# schematic.net
KiCad netlist of a schematic drawn in EAGLE
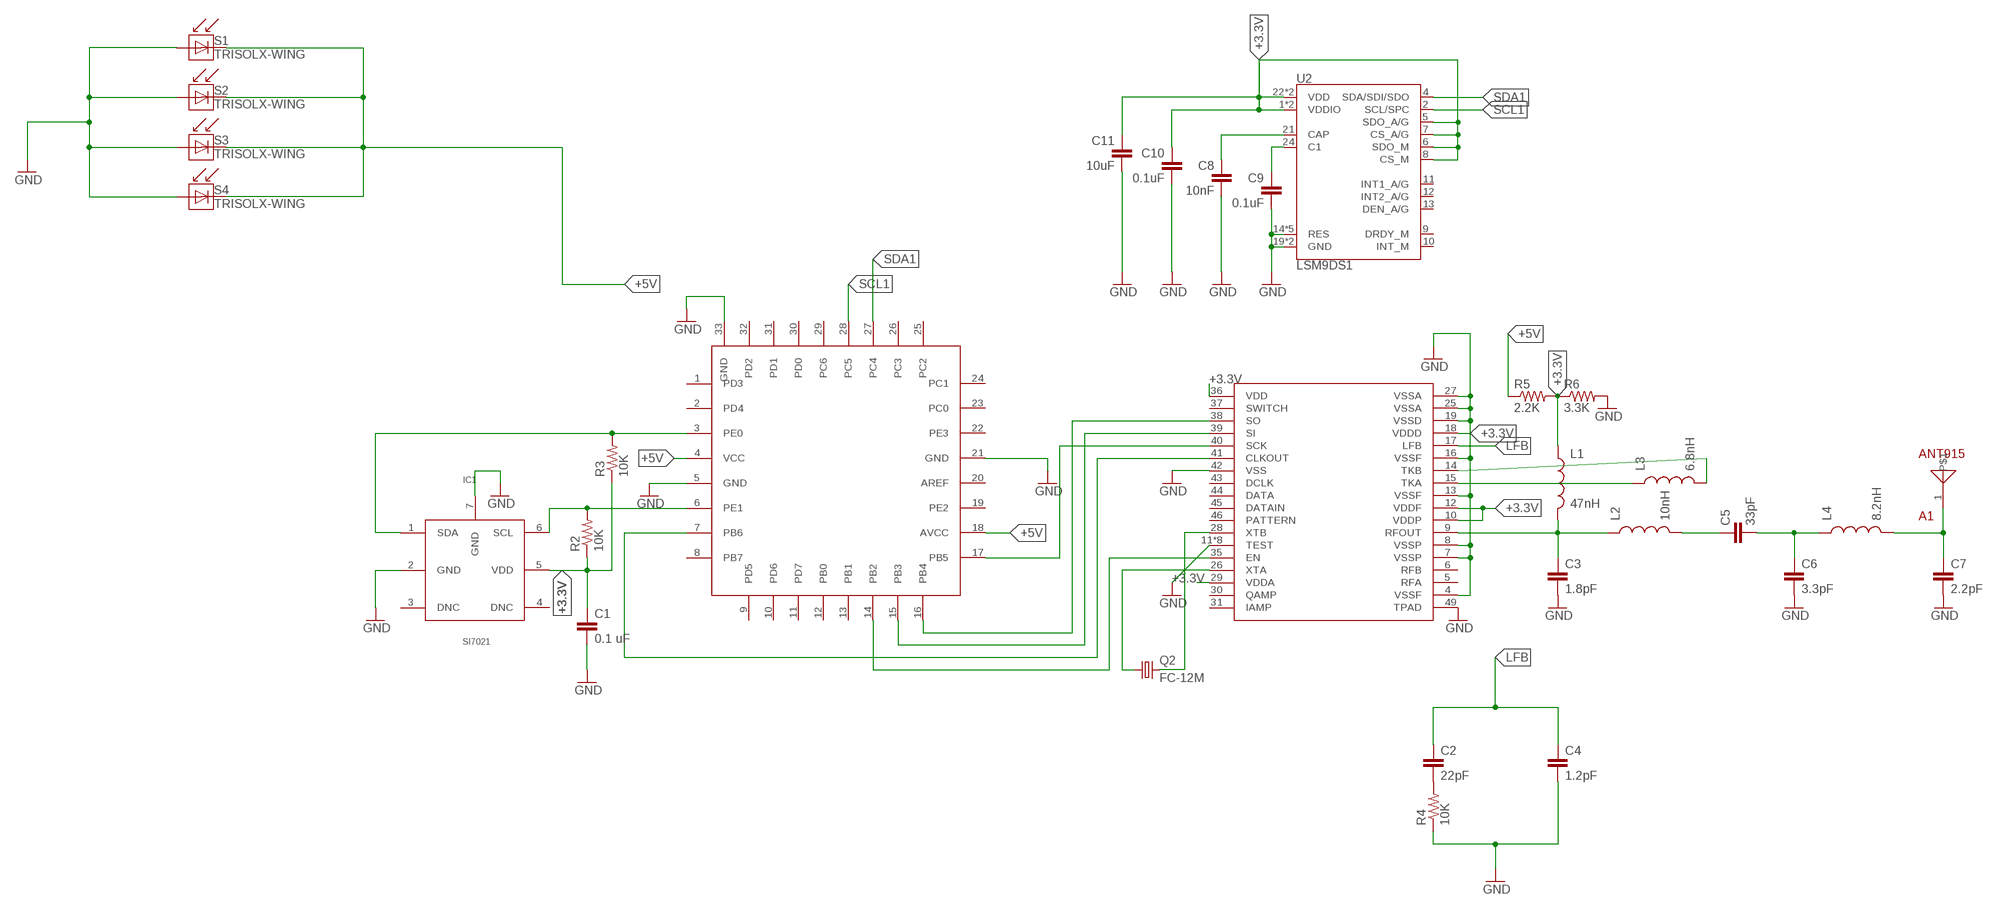
[diagram p0: schematic, sheet 1]

(export (version "E")
  (design (tool "Eeschema 10.0.6"))
  (components
    (comp (ref "A1")
      (value "ANT915")
      (footprint "eagle-import:ANT915")
      (libsource (lib "eagle-import") (part "ANT915"))
    )
    (comp (ref "C1")
      (value "0.1 uF")
      (footprint "eagle-import:0603-CAP")
      (libsource (lib "eagle-import") (part "CAP0603-CAP"))
    )
    (comp (ref "C2")
      (value "22pF")
      (footprint "eagle-import:0603-CAP")
      (libsource (lib "eagle-import") (part "CAP0603-CAP"))
    )
    (comp (ref "C3")
      (value "1.8pF")
      (footprint "eagle-import:0603-CAP")
      (libsource (lib "eagle-import") (part "CAP0603-CAP"))
    )
    (comp (ref "C4")
      (value "1.2pF")
      (footprint "eagle-import:0603-CAP")
      (libsource (lib "eagle-import") (part "CAP0603-CAP"))
    )
    (comp (ref "C5")
      (value "33pF")
      (footprint "eagle-import:0603-CAP")
      (libsource (lib "eagle-import") (part "CAP0603-CAP"))
    )
    (comp (ref "C6")
      (value "3.3pF")
      (footprint "eagle-import:0603-CAP")
      (libsource (lib "eagle-import") (part "CAP0603-CAP"))
    )
    (comp (ref "C7")
      (value "2.2pF")
      (footprint "eagle-import:0603-CAP")
      (libsource (lib "eagle-import") (part "CAP0603-CAP"))
    )
    (comp (ref "C8")
      (value "10nF")
      (footprint "eagle-import:0603-CAP")
      (libsource (lib "eagle-import") (part "CAP0603-CAP"))
    )
    (comp (ref "C9")
      (value "0.1uF")
      (footprint "eagle-import:0603-CAP")
      (libsource (lib "eagle-import") (part "CAP0603-CAP"))
    )
    (comp (ref "C10")
      (value "0.1uF")
      (footprint "eagle-import:0603-CAP")
      (libsource (lib "eagle-import") (part "CAP0603-CAP"))
    )
    (comp (ref "C11")
      (value "10uF")
      (footprint "eagle-import:0603-CAP")
      (libsource (lib "eagle-import") (part "CAP0603-CAP"))
    )
    (comp (ref "IC1")
      (value "SI7021")
      (footprint "eagle-import:SI7021")
      (libsource (lib "eagle-import") (part "SI7021"))
    )
    (comp (ref "IC2")
      (value "ATMEGA328-PB")
      (footprint "eagle-import:ATMEGA328-PB")
      (libsource (lib "eagle-import") (part "ATMEGA328-PB"))
    )
    (comp (ref "IC3")
      (value "XE1203F")
      (footprint "eagle-import:XE1203F")
      (libsource (lib "eagle-import") (part "XE1203F"))
    )
    (comp (ref "L1")
      (value "47nH")
      (footprint "eagle-import:0603")
      (libsource (lib "eagle-import") (part "INDUCTOR0603"))
    )
    (comp (ref "L2")
      (value "10nH")
      (footprint "eagle-import:0603")
      (libsource (lib "eagle-import") (part "INDUCTOR0603"))
    )
    (comp (ref "L3")
      (value "6.8nH")
      (footprint "eagle-import:0603")
      (libsource (lib "eagle-import") (part "INDUCTOR0603"))
    )
    (comp (ref "L4")
      (value "8.2nH")
      (footprint "eagle-import:0603")
      (libsource (lib "eagle-import") (part "INDUCTOR0603"))
    )
    (comp (ref "Q2")
      (value "FC-12M")
      (footprint "eagle-import:FC-12M")
      (libsource (lib "eagle-import") (part "FC-12M"))
    )
    (comp (ref "R2")
      (value "10K")
      (footprint "eagle-import:0603-RES")
      (libsource (lib "eagle-import") (part "RESISTOR0603-RES"))
    )
    (comp (ref "R3")
      (value "10K")
      (footprint "eagle-import:0603-RES")
      (libsource (lib "eagle-import") (part "RESISTOR0603-RES"))
    )
    (comp (ref "R4")
      (value "10K")
      (footprint "eagle-import:0603-RES")
      (libsource (lib "eagle-import") (part "RESISTOR0603-RES"))
    )
    (comp (ref "R5")
      (value "2.2K")
      (footprint "eagle-import:0603-RES")
      (libsource (lib "eagle-import") (part "RESISTOR0603-RES"))
    )
    (comp (ref "R6")
      (value "3.3K")
      (footprint "eagle-import:0603-RES")
      (libsource (lib "eagle-import") (part "RESISTOR0603-RES"))
    )
    (comp (ref "S1")
      (value "TRISOLX-WING")
      (footprint "eagle-import:TRISOLX-T01")
      (libsource (lib "eagle-import") (part "TRISOLX-WING"))
    )
    (comp (ref "S2")
      (value "TRISOLX-WING")
      (footprint "eagle-import:TRISOLX-T01")
      (libsource (lib "eagle-import") (part "TRISOLX-WING"))
    )
    (comp (ref "S3")
      (value "TRISOLX-WING")
      (footprint "eagle-import:TRISOLX-T01")
      (libsource (lib "eagle-import") (part "TRISOLX-WING"))
    )
    (comp (ref "S4")
      (value "TRISOLX-WING")
      (footprint "eagle-import:TRISOLX-T01")
      (libsource (lib "eagle-import") (part "TRISOLX-WING"))
    )
    (comp (ref "U2")
      (value "LSM9DS1")
      (footprint "eagle-import:LGA24-8X4")
      (libsource (lib "eagle-import") (part "LSM9DS1"))
    )
  )
  (nets
    (net (code "1") (name "+3.3V") (class "Default")
      (node (ref "C1") (pin "1") (pinfunction "1_1") (pintype "passive"))
      (node (ref "C10") (pin "1") (pinfunction "1_1") (pintype "passive"))
      (node (ref "C11") (pin "1") (pinfunction "1_1") (pintype "passive"))
      (node (ref "IC1") (pin "5") (pinfunction "VDD_5") (pintype "bidirectional"))
      (node (ref "IC3") (pin "10") (pinfunction "VDDP_10") (pintype "bidirectional"))
      (node (ref "IC3") (pin "12") (pinfunction "VDDF_12") (pintype "bidirectional"))
      (node (ref "IC3") (pin "18") (pinfunction "VDDD_18") (pintype "bidirectional"))
      (node (ref "IC3") (pin "29") (pinfunction "VDDA_29") (pintype "bidirectional"))
      (node (ref "IC3") (pin "36") (pinfunction "VDD_36") (pintype "bidirectional"))
      (node (ref "L1") (pin "1") (pinfunction "1_1") (pintype "passive"))
      (node (ref "R2") (pin "1") (pinfunction "1_1") (pintype "passive"))
      (node (ref "R3") (pin "1") (pinfunction "1_1") (pintype "passive"))
      (node (ref "R5") (pin "2") (pinfunction "2_2") (pintype "passive"))
      (node (ref "R6") (pin "1") (pinfunction "1_1") (pintype "passive"))
      (node (ref "U2") (pin "1") (pinfunction "VDDIO_1") (pintype "bidirectional"))
      (node (ref "U2") (pin "22") (pinfunction "VDD_22") (pintype "bidirectional"))
      (node (ref "U2") (pin "23") (pinfunction "VDD_23") (pintype "bidirectional"))
      (node (ref "U2") (pin "3") (pinfunction "VDDIO_3") (pintype "bidirectional"))
      (node (ref "U2") (pin "5") (pinfunction "SDO_A/G_5") (pintype "bidirectional"))
      (node (ref "U2") (pin "6") (pinfunction "SDO_M_6") (pintype "bidirectional"))
      (node (ref "U2") (pin "7") (pinfunction "CS_A/G_7") (pintype "bidirectional"))
      (node (ref "U2") (pin "8") (pinfunction "CS_M_8") (pintype "bidirectional"))
    )
    (net (code "2") (name "+5V") (class "Default")
      (node (ref "IC2") (pin "18") (pinfunction "AVCC_18") (pintype "bidirectional"))
      (node (ref "IC2") (pin "4") (pinfunction "VCC_4") (pintype "bidirectional"))
      (node (ref "R5") (pin "1") (pinfunction "1_1") (pintype "passive"))
      (node (ref "S1") (pin "P$2") (pinfunction "C_P$2") (pintype "passive"))
      (node (ref "S2") (pin "P$2") (pinfunction "C_P$2") (pintype "passive"))
      (node (ref "S3") (pin "P$2") (pinfunction "C_P$2") (pintype "passive"))
      (node (ref "S4") (pin "P$2") (pinfunction "C_P$2") (pintype "passive"))
    )
    (net (code "3") (name "GND") (class "Default")
      (node (ref "C1") (pin "2") (pinfunction "2_2") (pintype "passive"))
      (node (ref "C10") (pin "2") (pinfunction "2_2") (pintype "passive"))
      (node (ref "C11") (pin "2") (pinfunction "2_2") (pintype "passive"))
      (node (ref "C3") (pin "2") (pinfunction "2_2") (pintype "passive"))
      (node (ref "C4") (pin "2") (pinfunction "2_2") (pintype "passive"))
      (node (ref "C6") (pin "2") (pinfunction "2_2") (pintype "passive"))
      (node (ref "C7") (pin "2") (pinfunction "2_2") (pintype "passive"))
      (node (ref "C8") (pin "2") (pinfunction "2_2") (pintype "passive"))
      (node (ref "C9") (pin "2") (pinfunction "2_2") (pintype "passive"))
      (node (ref "IC1") (pin "2") (pinfunction "GND_2") (pintype "bidirectional"))
      (node (ref "IC1") (pin "7") (pinfunction "GND_7") (pintype "bidirectional"))
      (node (ref "IC2") (pin "21") (pinfunction "GND_21") (pintype "bidirectional"))
      (node (ref "IC2") (pin "33") (pinfunction "GND_33") (pintype "bidirectional"))
      (node (ref "IC2") (pin "5") (pinfunction "GND_5") (pintype "bidirectional"))
      (node (ref "IC3") (pin "11") (pinfunction "TEST_11") (pintype "bidirectional"))
      (node (ref "IC3") (pin "13") (pinfunction "VSSF_13") (pintype "bidirectional"))
      (node (ref "IC3") (pin "16") (pinfunction "VSSF_16") (pintype "bidirectional"))
      (node (ref "IC3") (pin "19") (pinfunction "VSSD_19") (pintype "bidirectional"))
      (node (ref "IC3") (pin "20") (pinfunction "TEST_20") (pintype "bidirectional"))
      (node (ref "IC3") (pin "21") (pinfunction "TEST_21") (pintype "bidirectional"))
      (node (ref "IC3") (pin "23") (pinfunction "TEST_23") (pintype "bidirectional"))
      (node (ref "IC3") (pin "24") (pinfunction "TEST_24") (pintype "bidirectional"))
      (node (ref "IC3") (pin "25") (pinfunction "VSSA_25") (pintype "bidirectional"))
      (node (ref "IC3") (pin "27") (pinfunction "VSSA_27") (pintype "bidirectional"))
      (node (ref "IC3") (pin "32") (pinfunction "TEST_32") (pintype "bidirectional"))
      (node (ref "IC3") (pin "33") (pinfunction "TEST_33") (pintype "bidirectional"))
      (node (ref "IC3") (pin "34") (pinfunction "TEST_34") (pintype "bidirectional"))
      (node (ref "IC3") (pin "4") (pinfunction "VSSF_4") (pintype "bidirectional"))
      (node (ref "IC3") (pin "42") (pinfunction "VSS_42") (pintype "bidirectional"))
      (node (ref "IC3") (pin "49") (pinfunction "TPAD_49") (pintype "bidirectional"))
      (node (ref "IC3") (pin "7") (pinfunction "VSSP_7") (pintype "bidirectional"))
      (node (ref "IC3") (pin "8") (pinfunction "VSSP_8") (pintype "bidirectional"))
      (node (ref "R4") (pin "1") (pinfunction "1_1") (pintype "passive"))
      (node (ref "R6") (pin "2") (pinfunction "2_2") (pintype "passive"))
      (node (ref "S1") (pin "P$3") (pinfunction "A_P$3") (pintype "passive"))
      (node (ref "S2") (pin "P$3") (pinfunction "A_P$3") (pintype "passive"))
      (node (ref "S3") (pin "P$3") (pinfunction "A_P$3") (pintype "passive"))
      (node (ref "S4") (pin "P$3") (pinfunction "A_P$3") (pintype "passive"))
      (node (ref "U2") (pin "14") (pinfunction "RES_14") (pintype "bidirectional"))
      (node (ref "U2") (pin "15") (pinfunction "RES_15") (pintype "bidirectional"))
      (node (ref "U2") (pin "16") (pinfunction "RES_16") (pintype "bidirectional"))
      (node (ref "U2") (pin "17") (pinfunction "RES_17") (pintype "bidirectional"))
      (node (ref "U2") (pin "18") (pinfunction "RES_18") (pintype "bidirectional"))
      (node (ref "U2") (pin "19") (pinfunction "GND_19") (pintype "bidirectional"))
      (node (ref "U2") (pin "20") (pinfunction "GND_20") (pintype "bidirectional"))
    )
    (net (code "4") (name "LFB") (class "Default")
      (node (ref "C2") (pin "1") (pinfunction "1_1") (pintype "passive"))
      (node (ref "C4") (pin "1") (pinfunction "1_1") (pintype "passive"))
      (node (ref "IC3") (pin "17") (pinfunction "LFB_17") (pintype "bidirectional"))
    )
    (net (code "5") (name "Net-(A1-P$1)") (class "Default")
      (node (ref "A1") (pin "1") (pinfunction "P$1_1") (pintype "bidirectional"))
      (node (ref "C7") (pin "1") (pinfunction "1_1") (pintype "passive"))
      (node (ref "L4") (pin "2") (pinfunction "2_2") (pintype "passive"))
    )
    (net (code "6") (name "Net-(C2-Pad2)") (class "Default")
      (node (ref "C2") (pin "2") (pinfunction "2_2") (pintype "passive"))
      (node (ref "R4") (pin "2") (pinfunction "2_2") (pintype "passive"))
    )
    (net (code "7") (name "Net-(C5-Pad1)") (class "Default")
      (node (ref "C5") (pin "1") (pinfunction "1_1") (pintype "passive"))
      (node (ref "L2") (pin "2") (pinfunction "2_2") (pintype "passive"))
    )
    (net (code "8") (name "Net-(C5-Pad2)") (class "Default")
      (node (ref "C5") (pin "2") (pinfunction "2_2") (pintype "passive"))
      (node (ref "C6") (pin "1") (pinfunction "1_1") (pintype "passive"))
      (node (ref "L4") (pin "1") (pinfunction "1_1") (pintype "passive"))
    )
    (net (code "9") (name "Net-(IC1-SCL)") (class "Default")
      (node (ref "IC1") (pin "6") (pinfunction "SCL_6") (pintype "bidirectional"))
      (node (ref "IC2") (pin "6") (pinfunction "PE1_6") (pintype "bidirectional"))
      (node (ref "R2") (pin "2") (pinfunction "2_2") (pintype "passive"))
    )
    (net (code "10") (name "Net-(IC1-SDA)") (class "Default")
      (node (ref "IC1") (pin "1") (pinfunction "SDA_1") (pintype "bidirectional"))
      (node (ref "IC2") (pin "3") (pinfunction "PE0_3") (pintype "bidirectional"))
      (node (ref "R3") (pin "2") (pinfunction "2_2") (pintype "passive"))
    )
    (net (code "11") (name "Net-(IC2-PB2)") (class "Default")
      (node (ref "IC2") (pin "14") (pinfunction "PB2_14") (pintype "bidirectional"))
      (node (ref "IC3") (pin "35") (pinfunction "EN_35") (pintype "bidirectional"))
    )
    (net (code "12") (name "Net-(IC2-PB3)") (class "Default")
      (node (ref "IC2") (pin "15") (pinfunction "PB3_15") (pintype "bidirectional"))
      (node (ref "IC3") (pin "39") (pinfunction "SI_39") (pintype "bidirectional"))
    )
    (net (code "13") (name "Net-(IC2-PB4)") (class "Default")
      (node (ref "IC2") (pin "16") (pinfunction "PB4_16") (pintype "bidirectional"))
      (node (ref "IC3") (pin "38") (pinfunction "SO_38") (pintype "bidirectional"))
    )
    (net (code "14") (name "Net-(IC2-PB5)") (class "Default")
      (node (ref "IC2") (pin "17") (pinfunction "PB5_17") (pintype "bidirectional"))
      (node (ref "IC3") (pin "40") (pinfunction "SCK_40") (pintype "bidirectional"))
    )
    (net (code "15") (name "Net-(IC2-PB6)") (class "Default")
      (node (ref "IC2") (pin "7") (pinfunction "PB6_7") (pintype "bidirectional"))
      (node (ref "IC3") (pin "41") (pinfunction "CLKOUT_41") (pintype "bidirectional"))
    )
    (net (code "16") (name "Net-(IC3-RFOUT)") (class "Default")
      (node (ref "C3") (pin "1") (pinfunction "1_1") (pintype "passive"))
      (node (ref "IC3") (pin "9") (pinfunction "RFOUT_9") (pintype "bidirectional"))
      (node (ref "L1") (pin "2") (pinfunction "2_2") (pintype "passive"))
      (node (ref "L2") (pin "1") (pinfunction "1_1") (pintype "passive"))
    )
    (net (code "17") (name "Net-(IC3-TKA)") (class "Default")
      (node (ref "IC3") (pin "15") (pinfunction "TKA_15") (pintype "bidirectional"))
      (node (ref "L3") (pin "1") (pinfunction "1_1") (pintype "passive"))
    )
    (net (code "18") (name "Net-(IC3-TKB)") (class "Default")
      (node (ref "IC3") (pin "14") (pinfunction "TKB_14") (pintype "bidirectional"))
      (node (ref "L3") (pin "2") (pinfunction "2_2") (pintype "passive"))
    )
    (net (code "19") (name "Net-(IC3-XTA)") (class "Default")
      (node (ref "IC3") (pin "26") (pinfunction "XTA_26") (pintype "bidirectional"))
      (node (ref "Q2") (pin "1") (pinfunction "1_1") (pintype "passive"))
    )
    (net (code "20") (name "Net-(IC3-XTB)") (class "Default")
      (node (ref "IC3") (pin "28") (pinfunction "XTB_28") (pintype "bidirectional"))
      (node (ref "Q2") (pin "2") (pinfunction "2_2") (pintype "passive"))
    )
    (net (code "21") (name "Net-(U2-C1)") (class "Default")
      (node (ref "C9") (pin "1") (pinfunction "1_1") (pintype "passive"))
      (node (ref "U2") (pin "24") (pinfunction "C1_24") (pintype "bidirectional"))
    )
    (net (code "22") (name "Net-(U2-CAP)") (class "Default")
      (node (ref "C8") (pin "1") (pinfunction "1_1") (pintype "passive"))
      (node (ref "U2") (pin "21") (pinfunction "CAP_21") (pintype "bidirectional"))
    )
    (net (code "23") (name "SCL1") (class "Default")
      (node (ref "IC2") (pin "28") (pinfunction "PC5_28") (pintype "bidirectional"))
      (node (ref "U2") (pin "2") (pinfunction "SCL/SPC_2") (pintype "bidirectional"))
    )
    (net (code "24") (name "SDA1") (class "Default")
      (node (ref "IC2") (pin "27") (pinfunction "PC4_27") (pintype "bidirectional"))
      (node (ref "U2") (pin "4") (pinfunction "SDA/SDI/SDO_4") (pintype "bidirectional"))
    )
    (net (code "25") (name "unconnected-(IC1-DNC-Pad3)") (class "Default")
      (node (ref "IC1") (pin "3") (pinfunction "DNC_3") (pintype "bidirectional"))
    )
    (net (code "26") (name "unconnected-(IC1-DNC-Pad4)") (class "Default")
      (node (ref "IC1") (pin "4") (pinfunction "DNC_4") (pintype "bidirectional"))
    )
    (net (code "27") (name "unconnected-(IC2-AREF-Pad20)") (class "Default")
      (node (ref "IC2") (pin "20") (pinfunction "AREF_20") (pintype "bidirectional"))
    )
    (net (code "28") (name "unconnected-(IC2-PB0-Pad12)") (class "Default")
      (node (ref "IC2") (pin "12") (pinfunction "PB0_12") (pintype "bidirectional"))
    )
    (net (code "29") (name "unconnected-(IC2-PB1-Pad13)") (class "Default")
      (node (ref "IC2") (pin "13") (pinfunction "PB1_13") (pintype "bidirectional"))
    )
    (net (code "30") (name "unconnected-(IC2-PB7-Pad8)") (class "Default")
      (node (ref "IC2") (pin "8") (pinfunction "PB7_8") (pintype "bidirectional"))
    )
    (net (code "31") (name "unconnected-(IC2-PC0-Pad23)") (class "Default")
      (node (ref "IC2") (pin "23") (pinfunction "PC0_23") (pintype "bidirectional"))
    )
    (net (code "32") (name "unconnected-(IC2-PC1-Pad24)") (class "Default")
      (node (ref "IC2") (pin "24") (pinfunction "PC1_24") (pintype "bidirectional"))
    )
    (net (code "33") (name "unconnected-(IC2-PC2-Pad25)") (class "Default")
      (node (ref "IC2") (pin "25") (pinfunction "PC2_25") (pintype "bidirectional"))
    )
    (net (code "34") (name "unconnected-(IC2-PC3-Pad26)") (class "Default")
      (node (ref "IC2") (pin "26") (pinfunction "PC3_26") (pintype "bidirectional"))
    )
    (net (code "35") (name "unconnected-(IC2-PC6-Pad29)") (class "Default")
      (node (ref "IC2") (pin "29") (pinfunction "PC6_29") (pintype "bidirectional"))
    )
    (net (code "36") (name "unconnected-(IC2-PD0-Pad30)") (class "Default")
      (node (ref "IC2") (pin "30") (pinfunction "PD0_30") (pintype "bidirectional"))
    )
    (net (code "37") (name "unconnected-(IC2-PD1-Pad31)") (class "Default")
      (node (ref "IC2") (pin "31") (pinfunction "PD1_31") (pintype "bidirectional"))
    )
    (net (code "38") (name "unconnected-(IC2-PD2-Pad32)") (class "Default")
      (node (ref "IC2") (pin "32") (pinfunction "PD2_32") (pintype "bidirectional"))
    )
    (net (code "39") (name "unconnected-(IC2-PD3-Pad1)") (class "Default")
      (node (ref "IC2") (pin "1") (pinfunction "PD3_1") (pintype "bidirectional"))
    )
    (net (code "40") (name "unconnected-(IC2-PD4-Pad2)") (class "Default")
      (node (ref "IC2") (pin "2") (pinfunction "PD4_2") (pintype "bidirectional"))
    )
    (net (code "41") (name "unconnected-(IC2-PD5-Pad9)") (class "Default")
      (node (ref "IC2") (pin "9") (pinfunction "PD5_9") (pintype "bidirectional"))
    )
    (net (code "42") (name "unconnected-(IC2-PD6-Pad10)") (class "Default")
      (node (ref "IC2") (pin "10") (pinfunction "PD6_10") (pintype "bidirectional"))
    )
    (net (code "43") (name "unconnected-(IC2-PD7-Pad11)") (class "Default")
      (node (ref "IC2") (pin "11") (pinfunction "PD7_11") (pintype "bidirectional"))
    )
    (net (code "44") (name "unconnected-(IC2-PE2-Pad19)") (class "Default")
      (node (ref "IC2") (pin "19") (pinfunction "PE2_19") (pintype "bidirectional"))
    )
    (net (code "45") (name "unconnected-(IC2-PE3-Pad22)") (class "Default")
      (node (ref "IC2") (pin "22") (pinfunction "PE3_22") (pintype "bidirectional"))
    )
    (net (code "46") (name "unconnected-(IC3-DATA-Pad44)") (class "Default")
      (node (ref "IC3") (pin "44") (pinfunction "DATA_44") (pintype "bidirectional"))
    )
    (net (code "47") (name "unconnected-(IC3-DATAIN-Pad45)") (class "Default")
      (node (ref "IC3") (pin "45") (pinfunction "DATAIN_45") (pintype "bidirectional"))
    )
    (net (code "48") (name "unconnected-(IC3-DCLK-Pad43)") (class "Default")
      (node (ref "IC3") (pin "43") (pinfunction "DCLK_43") (pintype "bidirectional"))
    )
    (net (code "49") (name "unconnected-(IC3-IAMP-Pad31)") (class "Default")
      (node (ref "IC3") (pin "31") (pinfunction "IAMP_31") (pintype "bidirectional"))
    )
    (net (code "50") (name "unconnected-(IC3-PATTERN-Pad46)") (class "Default")
      (node (ref "IC3") (pin "46") (pinfunction "PATTERN_46") (pintype "bidirectional"))
    )
    (net (code "51") (name "unconnected-(IC3-QAMP-Pad30)") (class "Default")
      (node (ref "IC3") (pin "30") (pinfunction "QAMP_30") (pintype "bidirectional"))
    )
    (net (code "52") (name "unconnected-(IC3-RFA-Pad5)") (class "Default")
      (node (ref "IC3") (pin "5") (pinfunction "RFA_5") (pintype "bidirectional"))
    )
    (net (code "53") (name "unconnected-(IC3-RFB-Pad6)") (class "Default")
      (node (ref "IC3") (pin "6") (pinfunction "RFB_6") (pintype "bidirectional"))
    )
    (net (code "54") (name "unconnected-(IC3-SWITCH-Pad37)") (class "Default")
      (node (ref "IC3") (pin "37") (pinfunction "SWITCH_37") (pintype "bidirectional"))
    )
    (net (code "55") (name "unconnected-(U2-DEN_A{slash}G-Pad13)") (class "Default")
      (node (ref "U2") (pin "13") (pinfunction "DEN_A/G_13") (pintype "bidirectional"))
    )
    (net (code "56") (name "unconnected-(U2-DRDY_M-Pad9)") (class "Default")
      (node (ref "U2") (pin "9") (pinfunction "DRDY_M_9") (pintype "bidirectional"))
    )
    (net (code "57") (name "unconnected-(U2-INT1_A{slash}G-Pad11)") (class "Default")
      (node (ref "U2") (pin "11") (pinfunction "INT1_A/G_11") (pintype "bidirectional"))
    )
    (net (code "58") (name "unconnected-(U2-INT2_A{slash}G-Pad12)") (class "Default")
      (node (ref "U2") (pin "12") (pinfunction "INT2_A/G_12") (pintype "bidirectional"))
    )
    (net (code "59") (name "unconnected-(U2-INT_M-Pad10)") (class "Default")
      (node (ref "U2") (pin "10") (pinfunction "INT_M_10") (pintype "bidirectional"))
    )
  )
)
